# QSPI.net
KiCad netlist of a schematic drawn in Altium Designer
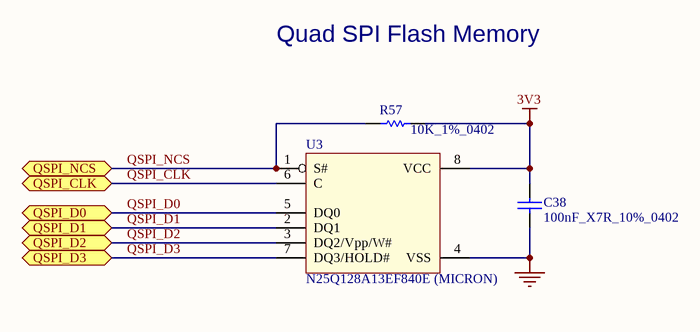
[diagram p0: QSPI.SchDoc]

(export (version "E")
  (design (tool "Eeschema 10.0.6"))
  (components
    (comp (ref "C38")
      (value "100nF_X7R_10%_0402")
      (footprint "0402C")
      (description "Capacitor,100nF,16V,X7R,10%,0402,YAGEO")
      (libsource (lib "MCD_TOOLS") (part "Cap_100nF_X7R_10%_0402"))
    )
    (comp (ref "R57")
      (value "10K_1%_0402")
      (footprint "0402R")
      (description "Resistor,10K,0402,1%,YAGEO")
      (libsource (lib "MCD_TOOLS") (part "Res_10K_1%_0402"))
    )
    (comp (ref "U3")
      (value "N25Q128A13EF840E (MICRON)")
      (footprint "V-PDFN-8 8x6")
      (description "128Mb, 3V, Multiple I/O Serial Flash Memory, Quad/Dual")
      (libsource (lib "MCD_TOOLS") (part "N25Q128A13EF840E"))
    )
  )
  (nets
    (net (code "1") (name "/QSPI_CLK") (class "Default")
      (node (ref "U3") (pin "6") (pinfunction "C_6") (pintype "passive"))
    )
    (net (code "2") (name "/QSPI_D0") (class "Default")
      (node (ref "U3") (pin "5") (pinfunction "DQ0_5") (pintype "passive"))
    )
    (net (code "3") (name "/QSPI_D1") (class "Default")
      (node (ref "U3") (pin "2") (pinfunction "DQ1_2") (pintype "passive"))
    )
    (net (code "4") (name "/QSPI_D2") (class "Default")
      (node (ref "U3") (pin "3") (pinfunction "DQ2/Vpp/W#_3") (pintype "passive"))
    )
    (net (code "5") (name "/QSPI_D3") (class "Default")
      (node (ref "U3") (pin "7") (pinfunction "DQ3/HOLD#_7") (pintype "passive"))
    )
    (net (code "6") (name "/QSPI_NCS") (class "Default")
      (node (ref "R57") (pin "1") (pinfunction "1_1") (pintype "passive"))
      (node (ref "U3") (pin "1") (pinfunction "S#_1") (pintype "passive"))
    )
    (net (code "7") (name "3V3") (class "Default")
      (node (ref "C38") (pin "2") (pinfunction "2_2") (pintype "passive"))
      (node (ref "R57") (pin "2") (pinfunction "2_2") (pintype "passive"))
      (node (ref "U3") (pin "8") (pinfunction "VCC_8") (pintype "passive"))
    )
    (net (code "8") (name "GND") (class "Default")
      (node (ref "C38") (pin "1") (pinfunction "1_1") (pintype "passive"))
      (node (ref "U3") (pin "4") (pinfunction "VSS_4") (pintype "passive"))
    )
  )
)
